# improved-handheld-turbidimeter_TIA.net
KiCad netlist of a schematic drawn in EAGLE
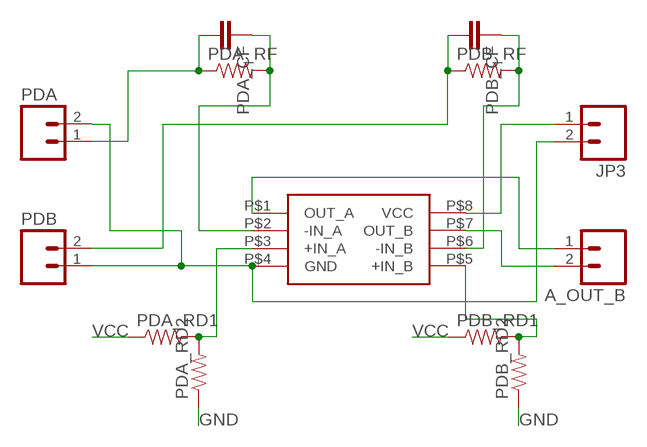
[diagram p0: schematic, sheet 1]

(export (version "E")
  (design (tool "Eeschema 10.0.6"))
  (components
    (comp (ref "A_OUT_B")
      (value "M02PTH")
      (footprint "eagle-import:1X02")
      (libsource (lib "eagle-import") (part "M02PTH"))
    )
    (comp (ref "JP3")
      (value "M02PTH")
      (footprint "eagle-import:1X02")
      (libsource (lib "eagle-import") (part "M02PTH"))
    )
    (comp (ref "PDA")
      (value "M02PTH")
      (footprint "eagle-import:1X02")
      (libsource (lib "eagle-import") (part "M02PTH"))
    )
    (comp (ref "PDA_CF")
      (value "CAP0603-CAP")
      (footprint "eagle-import:0603-CAP")
      (libsource (lib "eagle-import") (part "CAP0603-CAP"))
    )
    (comp (ref "PDA_RD1")
      (value "RESISTOR0603-RES")
      (footprint "eagle-import:0603-RES")
      (libsource (lib "eagle-import") (part "RESISTOR0603-RES"))
    )
    (comp (ref "PDA_RD2")
      (value "RESISTOR0603-RES")
      (footprint "eagle-import:0603-RES")
      (libsource (lib "eagle-import") (part "RESISTOR0603-RES"))
    )
    (comp (ref "PDA_RF")
      (value "RESISTOR0603-RES")
      (footprint "eagle-import:0603-RES")
      (libsource (lib "eagle-import") (part "RESISTOR0603-RES"))
    )
    (comp (ref "PDB")
      (value "M02PTH")
      (footprint "eagle-import:1X02")
      (libsource (lib "eagle-import") (part "M02PTH"))
    )
    (comp (ref "PDB_CF")
      (value "CAP0603-CAP")
      (footprint "eagle-import:0603-CAP")
      (libsource (lib "eagle-import") (part "CAP0603-CAP"))
    )
    (comp (ref "PDB_RD1")
      (value "RESISTOR0603-RES")
      (footprint "eagle-import:0603-RES")
      (libsource (lib "eagle-import") (part "RESISTOR0603-RES"))
    )
    (comp (ref "PDB_RD2")
      (value "RESISTOR0603-RES")
      (footprint "eagle-import:0603-RES")
      (libsource (lib "eagle-import") (part "RESISTOR0603-RES"))
    )
    (comp (ref "PDB_RF")
      (value "RESISTOR0603-RES")
      (footprint "eagle-import:0603-RES")
      (libsource (lib "eagle-import") (part "RESISTOR0603-RES"))
    )
    (comp (ref "U$2")
      (value "ADA4528-2")
      (footprint "eagle-import:ADA4528-2")
      (libsource (lib "eagle-import") (part "ADA4528-2"))
    )
  )
  (nets
    (net (code "1") (name "/GND") (class "Default")
      (node (ref "JP3") (pin "2") (pinfunction "2_2") (pintype "passive"))
      (node (ref "PDA") (pin "2") (pinfunction "2_2") (pintype "passive"))
      (node (ref "PDA_RD2") (pin "1") (pinfunction "1_1") (pintype "passive"))
      (node (ref "PDB") (pin "1") (pinfunction "1_1") (pintype "passive"))
      (node (ref "PDB_RD2") (pin "1") (pinfunction "1_1") (pintype "passive"))
      (node (ref "U$2") (pin "P$4") (pinfunction "GND_P$4") (pintype "bidirectional"))
    )
    (net (code "2") (name "/VCC") (class "Default")
      (node (ref "JP3") (pin "1") (pinfunction "1_1") (pintype "passive"))
      (node (ref "PDA_RD1") (pin "1") (pinfunction "1_1") (pintype "passive"))
      (node (ref "PDB_RD1") (pin "1") (pinfunction "1_1") (pintype "passive"))
      (node (ref "U$2") (pin "P$8") (pinfunction "VCC_P$8") (pintype "bidirectional"))
    )
    (net (code "3") (name "Net-(PDA-Pad1)") (class "Default")
      (node (ref "PDA") (pin "1") (pinfunction "1_1") (pintype "passive"))
      (node (ref "PDA_CF") (pin "2") (pinfunction "2_2") (pintype "passive"))
      (node (ref "PDA_RF") (pin "1") (pinfunction "1_1") (pintype "passive"))
    )
    (net (code "4") (name "Net-(PDB-Pad2)") (class "Default")
      (node (ref "PDB") (pin "2") (pinfunction "2_2") (pintype "passive"))
      (node (ref "PDB_CF") (pin "2") (pinfunction "2_2") (pintype "passive"))
      (node (ref "PDB_RF") (pin "1") (pinfunction "1_1") (pintype "passive"))
    )
    (net (code "5") (name "Net-(U$2-+IN_A)") (class "Default")
      (node (ref "PDA_RD1") (pin "2") (pinfunction "2_2") (pintype "passive"))
      (node (ref "PDA_RD2") (pin "2") (pinfunction "2_2") (pintype "passive"))
      (node (ref "U$2") (pin "P$3") (pinfunction "+IN_A_P$3") (pintype "bidirectional"))
    )
    (net (code "6") (name "Net-(U$2-+IN_B)") (class "Default")
      (node (ref "PDB_RD1") (pin "2") (pinfunction "2_2") (pintype "passive"))
      (node (ref "PDB_RD2") (pin "2") (pinfunction "2_2") (pintype "passive"))
      (node (ref "U$2") (pin "P$5") (pinfunction "+IN_B_P$5") (pintype "bidirectional"))
    )
    (net (code "7") (name "Net-(U$2--IN_A)") (class "Default")
      (node (ref "PDA_CF") (pin "1") (pinfunction "1_1") (pintype "passive"))
      (node (ref "PDA_RF") (pin "2") (pinfunction "2_2") (pintype "passive"))
      (node (ref "U$2") (pin "P$2") (pinfunction "-IN_A_P$2") (pintype "bidirectional"))
    )
    (net (code "8") (name "Net-(U$2--IN_B)") (class "Default")
      (node (ref "PDB_CF") (pin "1") (pinfunction "1_1") (pintype "passive"))
      (node (ref "PDB_RF") (pin "2") (pinfunction "2_2") (pintype "passive"))
      (node (ref "U$2") (pin "P$6") (pinfunction "-IN_B_P$6") (pintype "bidirectional"))
    )
    (net (code "9") (name "Net-(U$2-OUT_A)") (class "Default")
      (node (ref "A_OUT_B") (pin "1") (pinfunction "1_1") (pintype "passive"))
      (node (ref "U$2") (pin "P$1") (pinfunction "OUT_A_P$1") (pintype "bidirectional"))
    )
    (net (code "10") (name "Net-(U$2-OUT_B)") (class "Default")
      (node (ref "A_OUT_B") (pin "2") (pinfunction "2_2") (pintype "passive"))
      (node (ref "U$2") (pin "P$7") (pinfunction "OUT_B_P$7") (pintype "bidirectional"))
    )
  )
)
